# 02_USB_Bridge.net
KiCad netlist of a schematic drawn in Altium Designer
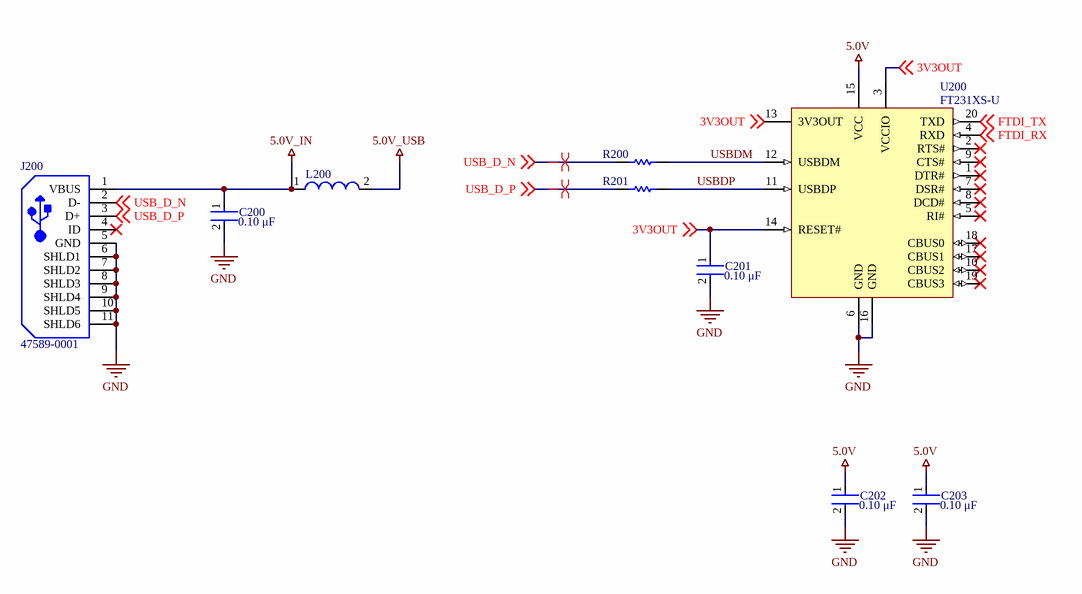
[diagram p0: 02_USB_Bridge.SchDoc]

(export (version "E")
  (design (tool "Eeschema 10.0.6"))
  (components
    (comp (ref "C200")
      (value "0.10 μF")
      (footprint "FP-C0805C-DN-MFG")
      (description "CAP CER 0.1UF 50V X7R 0805")
      (fields
        (field (name "MANUFACTURER") "KEMET")
        (field (name "MANUFACTURER PART NUMBER") "C0805C104K5RACTU")
      )
      (libsource (lib "Altium Content Vault") (part "b4654b650e69147ec39a6b967a45e02"))
    )
    (comp (ref "C201")
      (value "0.10 μF")
      (footprint "FP-C0805C-DN-MFG")
      (description "CAP CER 0.1UF 50V X7R 0805")
      (fields
        (field (name "MANUFACTURER") "KEMET")
        (field (name "MANUFACTURER PART NUMBER") "C0805C104K5RACTU")
      )
      (libsource (lib "Altium Content Vault") (part "b4654b650e69147ec39a6b967a45e02"))
    )
    (comp (ref "C202")
      (value "0.10 μF")
      (footprint "FP-C0805C-DN-MFG")
      (description "CAP CER 0.1UF 50V X7R 0805")
      (fields
        (field (name "MANUFACTURER") "KEMET")
        (field (name "MANUFACTURER PART NUMBER") "C0805C104K5RACTU")
      )
      (libsource (lib "Altium Content Vault") (part "b4654b650e69147ec39a6b967a45e02"))
    )
    (comp (ref "C203")
      (value "0.10 μF")
      (footprint "FP-C0805C-DN-MFG")
      (description "CAP CER 0.1UF 50V X7R 0805")
      (fields
        (field (name "MANUFACTURER") "KEMET")
        (field (name "MANUFACTURER PART NUMBER") "C0805C104K5RACTU")
      )
      (libsource (lib "Altium Content Vault") (part "b4654b650e69147ec39a6b967a45e02"))
    )
    (comp (ref "J200")
      (value "47589-0001")
      (footprint "MOLX-47589-0001_V")
      (description "Right Angle Female Type AB Micro USB Connector, 30 V, 1.8 A, -30 to 85 degC, RoHS, Tape and Reel")
      (fields (field (name "MANUFACTURER") "Molex"))
      (libsource (lib "Altium Content Vault") (part "USB-5-6SHLD"))
    )
    (comp (ref "L200")
      (value "742792093")
      (footprint "SMD-0805")
      (description "SMD EMI Suppression Ferrite Bead WE-CBF, Z = 2200 Ohm")
      (libsource (lib "Altium Content Vault") (part "PAS-IND-INDUCTOR-2"))
    )
    (comp (ref "R200")
      (value "ERJ6ENF27R0V")
      (footprint "RESC2013X70X40ML20T20")
      (fields (field (name "MANUFACTURER") "Panasonic"))
      (libsource (lib "Altium Content Vault") (part "RES"))
    )
    (comp (ref "R201")
      (value "ERJ6ENF27R0V")
      (footprint "RESC2013X70X40ML20T20")
      (fields (field (name "MANUFACTURER") "Panasonic"))
      (libsource (lib "Altium Content Vault") (part "RES"))
    )
    (comp (ref "U200")
      (value "FT231XS-U")
      (footprint "SSOP-20_L")
      (fields (field (name "MANUFACTURER") "FTDI"))
      (libsource (lib "Altium Content Vault") (part "COM-USB-FT231XS-IL20"))
    )
  )
  (nets
    (net (code "1") (name "/USBDM") (class "Default")
      (node (ref "R200") (pin "2") (pinfunction "2_2") (pintype "passive"))
      (node (ref "U200") (pin "12") (pinfunction "USBDM_12") (pintype "input"))
    )
    (net (code "2") (name "/USBDP") (class "Default")
      (node (ref "R201") (pin "2") (pinfunction "2_2") (pintype "passive"))
      (node (ref "U200") (pin "11") (pinfunction "USBDP_11") (pintype "input"))
    )
    (net (code "3") (name "3V3OUT") (class "Default")
      (node (ref "C201") (pin "1") (pinfunction "1_1") (pintype "passive"))
      (node (ref "U200") (pin "13") (pinfunction "3V3OUT_13") (pintype "power_in"))
      (node (ref "U200") (pin "14") (pinfunction "RESET#_14") (pintype "input"))
      (node (ref "U200") (pin "3") (pinfunction "VCCIO_3") (pintype "power_in"))
    )
    (net (code "4") (name "5.0V") (class "Default")
      (node (ref "C202") (pin "1") (pinfunction "1_1") (pintype "passive"))
      (node (ref "C203") (pin "1") (pinfunction "1_1") (pintype "passive"))
      (node (ref "U200") (pin "15") (pinfunction "VCC_15") (pintype "power_in"))
    )
    (net (code "5") (name "5.0V_IN") (class "Default")
      (node (ref "C200") (pin "1") (pinfunction "1_1") (pintype "passive"))
      (node (ref "J200") (pin "1") (pinfunction "VBUS_1") (pintype "passive"))
      (node (ref "L200") (pin "1") (pinfunction "1_1") (pintype "passive"))
    )
    (net (code "6") (name "5.0V_USB") (class "Default")
      (node (ref "L200") (pin "2") (pinfunction "2_2") (pintype "passive"))
    )
    (net (code "7") (name "FTDI_RX") (class "Default")
      (node (ref "U200") (pin "4") (pinfunction "RXD_4") (pintype "input"))
    )
    (net (code "8") (name "FTDI_TX") (class "Default")
      (node (ref "U200") (pin "20") (pinfunction "TXD_20") (pintype "output"))
    )
    (net (code "9") (name "GND") (class "Default")
      (node (ref "C200") (pin "2") (pinfunction "2_2") (pintype "passive"))
      (node (ref "C201") (pin "2") (pinfunction "2_2") (pintype "passive"))
      (node (ref "C202") (pin "2") (pinfunction "2_2") (pintype "passive"))
      (node (ref "C203") (pin "2") (pinfunction "2_2") (pintype "passive"))
      (node (ref "J200") (pin "10") (pinfunction "SHLD5_10") (pintype "passive"))
      (node (ref "J200") (pin "11") (pinfunction "SHLD6_11") (pintype "passive"))
      (node (ref "J200") (pin "5") (pinfunction "GND_5") (pintype "passive"))
      (node (ref "J200") (pin "6") (pinfunction "SHLD1_6") (pintype "passive"))
      (node (ref "J200") (pin "7") (pinfunction "SHLD2_7") (pintype "passive"))
      (node (ref "J200") (pin "8") (pinfunction "SHLD3_8") (pintype "passive"))
      (node (ref "J200") (pin "9") (pinfunction "SHLD4_9") (pintype "passive"))
      (node (ref "U200") (pin "16") (pinfunction "GND_16") (pintype "power_in"))
      (node (ref "U200") (pin "6") (pinfunction "GND_6") (pintype "power_in"))
    )
    (net (code "10") (name "USB_D_N") (class "Default")
      (node (ref "J200") (pin "2") (pinfunction "D-_2") (pintype "passive"))
      (node (ref "R200") (pin "1") (pinfunction "1_1") (pintype "passive"))
    )
    (net (code "11") (name "USB_D_P") (class "Default")
      (node (ref "J200") (pin "3") (pinfunction "D+_3") (pintype "passive"))
      (node (ref "R201") (pin "1") (pinfunction "1_1") (pintype "passive"))
    )
    (net (code "12") (name "unconnected-(J200-ID-Pad4)") (class "Default")
      (node (ref "J200") (pin "4") (pinfunction "ID_4") (pintype "passive+no_connect"))
    )
    (net (code "13") (name "unconnected-(U200-CBUS0-Pad18)") (class "Default")
      (node (ref "U200") (pin "18") (pinfunction "CBUS0_18") (pintype "bidirectional+no_connect"))
    )
    (net (code "14") (name "unconnected-(U200-CBUS1-Pad17)") (class "Default")
      (node (ref "U200") (pin "17") (pinfunction "CBUS1_17") (pintype "bidirectional+no_connect"))
    )
    (net (code "15") (name "unconnected-(U200-CBUS2-Pad10)") (class "Default")
      (node (ref "U200") (pin "10") (pinfunction "CBUS2_10") (pintype "bidirectional+no_connect"))
    )
    (net (code "16") (name "unconnected-(U200-CBUS3-Pad19)") (class "Default")
      (node (ref "U200") (pin "19") (pinfunction "CBUS3_19") (pintype "bidirectional+no_connect"))
    )
    (net (code "17") (name "unconnected-(U200-CTS#-Pad9)") (class "Default")
      (node (ref "U200") (pin "9") (pinfunction "CTS#_9") (pintype "input+no_connect"))
    )
    (net (code "18") (name "unconnected-(U200-DCD#-Pad8)") (class "Default")
      (node (ref "U200") (pin "8") (pinfunction "DCD#_8") (pintype "input+no_connect"))
    )
    (net (code "19") (name "unconnected-(U200-DSR#-Pad7)") (class "Default")
      (node (ref "U200") (pin "7") (pinfunction "DSR#_7") (pintype "input+no_connect"))
    )
    (net (code "20") (name "unconnected-(U200-DTR#-Pad1)") (class "Default")
      (node (ref "U200") (pin "1") (pinfunction "DTR#_1") (pintype "output+no_connect"))
    )
    (net (code "21") (name "unconnected-(U200-RI#-Pad5)") (class "Default")
      (node (ref "U200") (pin "5") (pinfunction "RI#_5") (pintype "input+no_connect"))
    )
    (net (code "22") (name "unconnected-(U200-RTS#-Pad2)") (class "Default")
      (node (ref "U200") (pin "2") (pinfunction "RTS#_2") (pintype "output+no_connect"))
    )
  )
)
